# PHR_revA.net
KiCad netlist of a schematic drawn in EAGLE
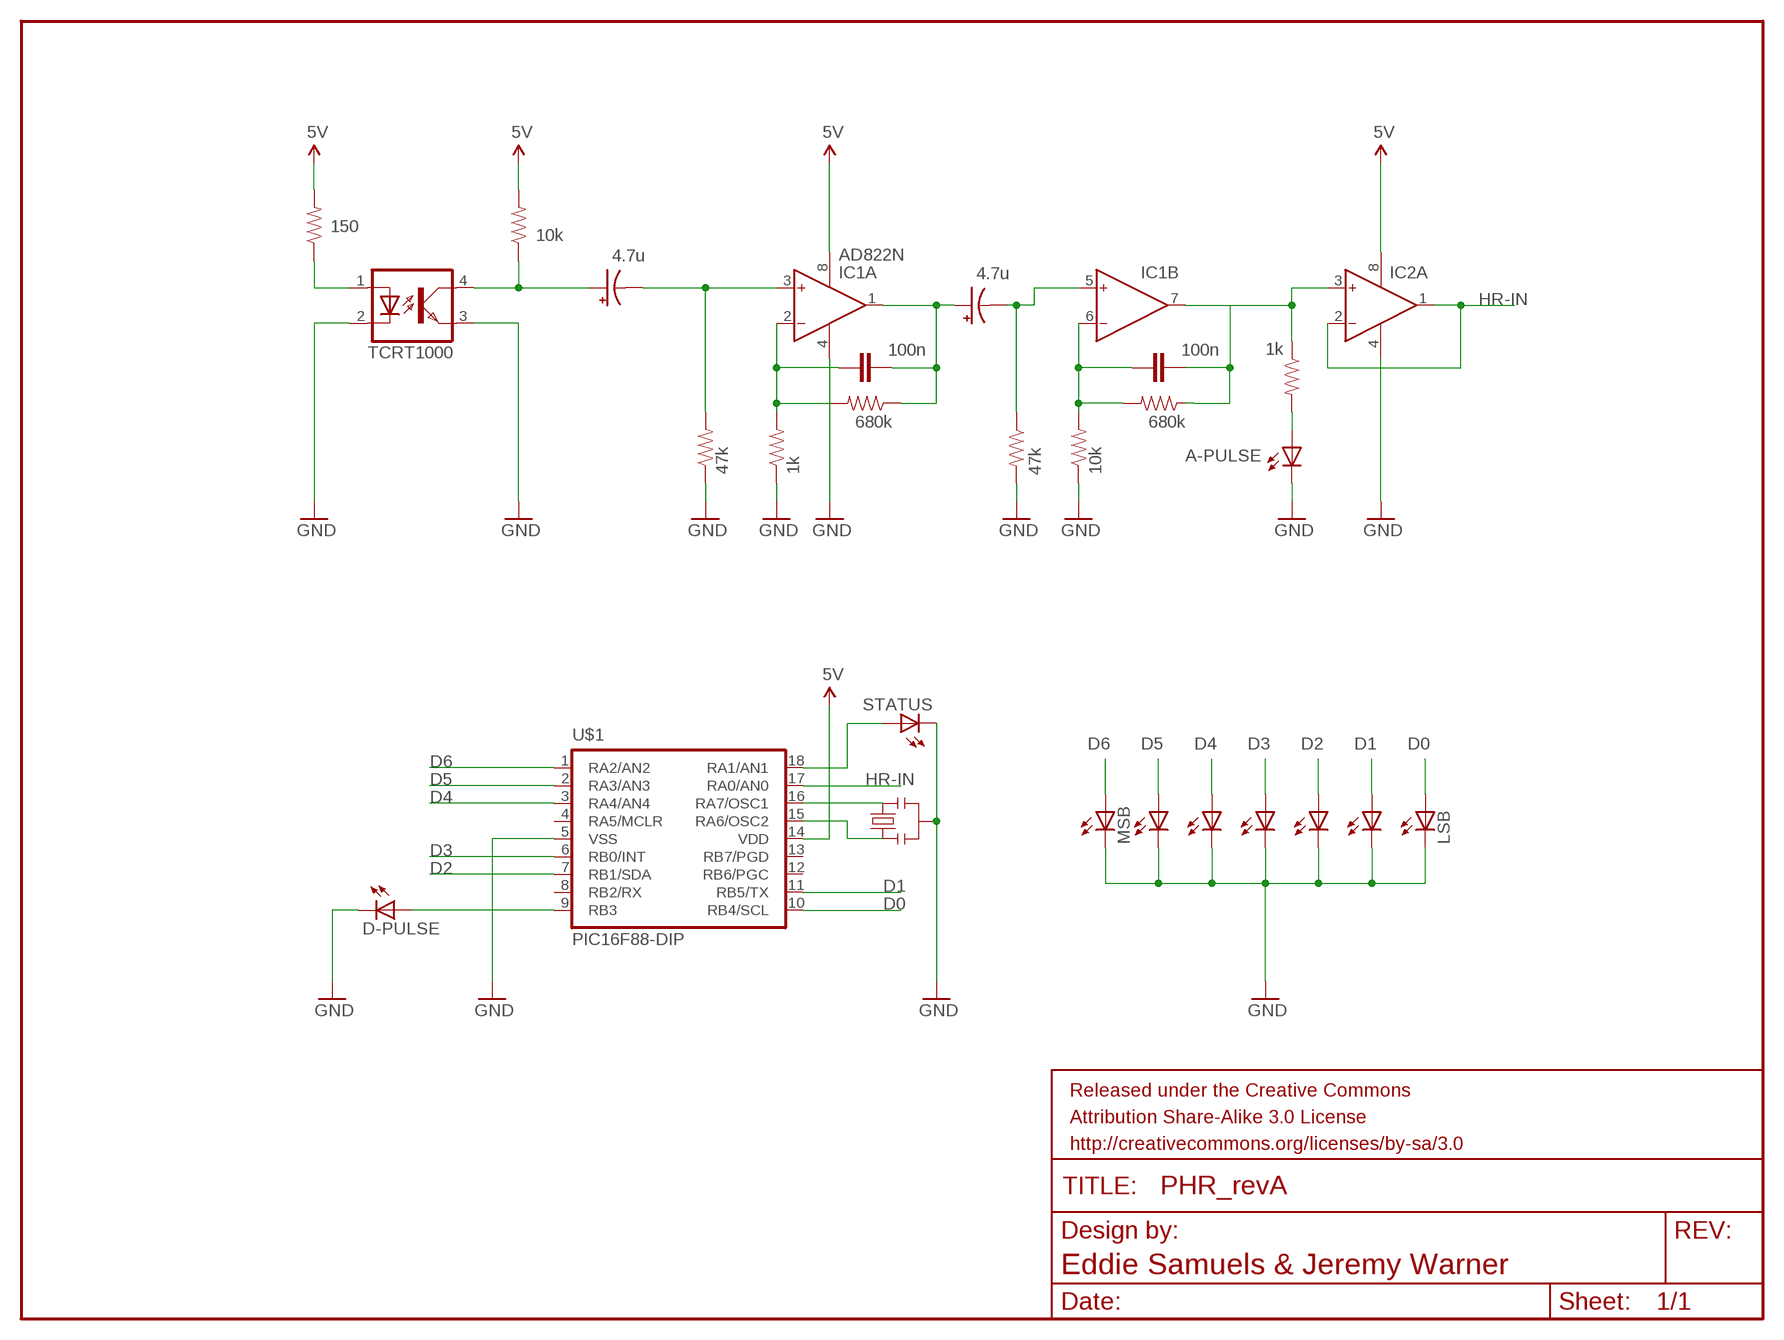
[diagram p0: schematic, sheet 1]

(export (version "E")
  (design (tool "Eeschema 10.0.6"))
  (components
    (comp (ref "A-PULSE")
      (value "LED3MM")
      (footprint "eagle-import:LED3MM")
      (libsource (lib "eagle-import") (part "LED3MM"))
    )
    (comp (ref "C1")
      (value "100n")
      (footprint "eagle-import:CAP-PTH-SMALL-KIT")
      (libsource (lib "eagle-import") (part "CAPKIT"))
    )
    (comp (ref "C2")
      (value "100n")
      (footprint "eagle-import:CAP-PTH-SMALL-KIT")
      (libsource (lib "eagle-import") (part "CAPKIT"))
    )
    (comp (ref "C3")
      (value "4.7u")
      (footprint "eagle-import:CPOL-RADIAL-10UF-25V")
      (libsource (lib "eagle-import") (part "CAP_POLPTH2"))
    )
    (comp (ref "C4")
      (value "4.7u")
      (footprint "eagle-import:CPOL-RADIAL-10UF-25V")
      (libsource (lib "eagle-import") (part "CAP_POLPTH2"))
    )
    (comp (ref "D-PULSE")
      (value "LED3MM")
      (footprint "eagle-import:LED3MM")
      (libsource (lib "eagle-import") (part "LED3MM"))
    )
    (comp (ref "D1")
      (value "LED3MM")
      (footprint "eagle-import:LED3MM")
      (libsource (lib "eagle-import") (part "LED3MM"))
    )
    (comp (ref "D2")
      (value "LED3MM")
      (footprint "eagle-import:LED3MM")
      (libsource (lib "eagle-import") (part "LED3MM"))
    )
    (comp (ref "D3")
      (value "LED3MM")
      (footprint "eagle-import:LED3MM")
      (libsource (lib "eagle-import") (part "LED3MM"))
    )
    (comp (ref "D4")
      (value "LED3MM")
      (footprint "eagle-import:LED3MM")
      (libsource (lib "eagle-import") (part "LED3MM"))
    )
    (comp (ref "D5")
      (value "LED3MM")
      (footprint "eagle-import:LED3MM")
      (libsource (lib "eagle-import") (part "LED3MM"))
    )
    (comp (ref "FRAME1")
      (value "FRAME-LETTER")
      (footprint "eagle-import:CREATIVE_COMMONS")
      (libsource (lib "eagle-import") (part "FRAME-LETTER"))
    )
    (comp (ref "IC1")
      (value "AD822N")
      (footprint "eagle-import:DIL08")
      (libsource (lib "eagle-import") (part "AD822N"))
    )
    (comp (ref "IC2")
      (value "AD822N")
      (footprint "eagle-import:DIL08")
      (libsource (lib "eagle-import") (part "AD822N"))
    )
    (comp (ref "LSB")
      (value "LED3MM")
      (footprint "eagle-import:LED3MM")
      (libsource (lib "eagle-import") (part "LED3MM"))
    )
    (comp (ref "MSB")
      (value "LED3MM")
      (footprint "eagle-import:LED3MM")
      (libsource (lib "eagle-import") (part "LED3MM"))
    )
    (comp (ref "OK1")
      (value "SFH618A-2")
      (footprint "eagle-import:DIP4")
      (fields (field (name "MF") "VISHAY/TELEFUNKEN"))
      (libsource (lib "eagle-import") (part "SFH618?A-2"))
    )
    (comp (ref "R1")
      (value "47k")
      (footprint "eagle-import:AXIAL-0.4")
      (libsource (lib "eagle-import") (part "RESISTORPTH-1/4W"))
    )
    (comp (ref "R2")
      (value "1k")
      (footprint "eagle-import:AXIAL-0.4")
      (libsource (lib "eagle-import") (part "RESISTORPTH-1/4W"))
    )
    (comp (ref "R3")
      (value "680k")
      (footprint "eagle-import:AXIAL-0.4")
      (libsource (lib "eagle-import") (part "RESISTORPTH-1/4W"))
    )
    (comp (ref "R4")
      (value "47k")
      (footprint "eagle-import:AXIAL-0.4")
      (libsource (lib "eagle-import") (part "RESISTORPTH-1/4W"))
    )
    (comp (ref "R5")
      (value "10k")
      (footprint "eagle-import:AXIAL-0.4")
      (libsource (lib "eagle-import") (part "RESISTORPTH-1/4W"))
    )
    (comp (ref "R6")
      (value "680k")
      (footprint "eagle-import:AXIAL-0.4")
      (libsource (lib "eagle-import") (part "RESISTORPTH-1/4W"))
    )
    (comp (ref "R7")
      (value "10k")
      (footprint "eagle-import:AXIAL-0.4")
      (libsource (lib "eagle-import") (part "RESISTORPTH-1/4W"))
    )
    (comp (ref "R8")
      (value "150")
      (footprint "eagle-import:AXIAL-0.4")
      (libsource (lib "eagle-import") (part "RESISTORPTH-1/4W"))
    )
    (comp (ref "R9")
      (value "1k")
      (footprint "eagle-import:AXIAL-0.4")
      (libsource (lib "eagle-import") (part "RESISTORPTH-1/4W"))
    )
    (comp (ref "STATUS")
      (value "LED3MM")
      (footprint "eagle-import:LED3MM")
      (libsource (lib "eagle-import") (part "LED3MM"))
    )
    (comp (ref "U$1")
      (value "PIC16F88-DIP")
      (footprint "eagle-import:DIL18")
      (libsource (lib "eagle-import") (part "PIC16F88-DIP"))
    )
    (comp (ref "Y1")
      (value "RESONATORPTH")
      (footprint "eagle-import:RESONATOR-PTH")
      (libsource (lib "eagle-import") (part "RESONATORPTH"))
    )
  )
  (nets
    (net (code "1") (name "/D0") (class "Default")
      (node (ref "LSB") (pin "A") (pinfunction "A_A") (pintype "passive"))
      (node (ref "U$1") (pin "10") (pinfunction "RB4/SCL_10") (pintype "bidirectional"))
    )
    (net (code "2") (name "/D1") (class "Default")
      (node (ref "D5") (pin "A") (pinfunction "A_A") (pintype "passive"))
      (node (ref "U$1") (pin "11") (pinfunction "RB5/TX_11") (pintype "bidirectional"))
    )
    (net (code "3") (name "/D2") (class "Default")
      (node (ref "D4") (pin "A") (pinfunction "A_A") (pintype "passive"))
      (node (ref "U$1") (pin "7") (pinfunction "RB1/SDA_7") (pintype "bidirectional"))
    )
    (net (code "4") (name "/D3") (class "Default")
      (node (ref "D3") (pin "A") (pinfunction "A_A") (pintype "passive"))
      (node (ref "U$1") (pin "6") (pinfunction "RB0/INT_6") (pintype "bidirectional"))
    )
    (net (code "5") (name "/D4") (class "Default")
      (node (ref "D2") (pin "A") (pinfunction "A_A") (pintype "passive"))
      (node (ref "U$1") (pin "3") (pinfunction "RA4/AN4_3") (pintype "bidirectional"))
    )
    (net (code "6") (name "/D5") (class "Default")
      (node (ref "D1") (pin "A") (pinfunction "A_A") (pintype "passive"))
      (node (ref "U$1") (pin "2") (pinfunction "RA3/AN3_2") (pintype "bidirectional"))
    )
    (net (code "7") (name "/D6") (class "Default")
      (node (ref "MSB") (pin "A") (pinfunction "A_A") (pintype "passive"))
      (node (ref "U$1") (pin "1") (pinfunction "RA2/AN2_1") (pintype "bidirectional"))
    )
    (net (code "8") (name "/HR-IN") (class "Default")
      (node (ref "IC2") (pin "1") (pinfunction "OUT_1") (pintype "output"))
      (node (ref "IC2") (pin "2") (pinfunction "IN-_2") (pintype "input"))
      (node (ref "U$1") (pin "17") (pinfunction "RA0/AN0_17") (pintype "bidirectional"))
    )
    (net (code "9") (name "5V") (class "Default")
      (node (ref "IC1") (pin "8") (pinfunction "V+_8") (pintype "power_in"))
      (node (ref "IC2") (pin "8") (pinfunction "V+_8") (pintype "power_in"))
      (node (ref "R7") (pin "P$2") (pinfunction "2_P$2") (pintype "passive"))
      (node (ref "R8") (pin "P$2") (pinfunction "2_P$2") (pintype "passive"))
      (node (ref "U$1") (pin "14") (pinfunction "VDD_14") (pintype "power_in"))
    )
    (net (code "10") (name "GND") (class "Default")
      (node (ref "A-PULSE") (pin "K") (pinfunction "C_K") (pintype "passive"))
      (node (ref "D-PULSE") (pin "K") (pinfunction "C_K") (pintype "passive"))
      (node (ref "D1") (pin "K") (pinfunction "C_K") (pintype "passive"))
      (node (ref "D2") (pin "K") (pinfunction "C_K") (pintype "passive"))
      (node (ref "D3") (pin "K") (pinfunction "C_K") (pintype "passive"))
      (node (ref "D4") (pin "K") (pinfunction "C_K") (pintype "passive"))
      (node (ref "D5") (pin "K") (pinfunction "C_K") (pintype "passive"))
      (node (ref "IC1") (pin "4") (pinfunction "V-_4") (pintype "power_in"))
      (node (ref "IC2") (pin "4") (pinfunction "V-_4") (pintype "power_in"))
      (node (ref "LSB") (pin "K") (pinfunction "C_K") (pintype "passive"))
      (node (ref "MSB") (pin "K") (pinfunction "C_K") (pintype "passive"))
      (node (ref "OK1") (pin "2") (pinfunction "C_2") (pintype "passive"))
      (node (ref "OK1") (pin "3") (pinfunction "EMIT_3") (pintype "passive"))
      (node (ref "R1") (pin "P$1") (pinfunction "1_P$1") (pintype "passive"))
      (node (ref "R2") (pin "P$1") (pinfunction "1_P$1") (pintype "passive"))
      (node (ref "R4") (pin "P$2") (pinfunction "2_P$2") (pintype "passive"))
      (node (ref "R5") (pin "P$1") (pinfunction "1_P$1") (pintype "passive"))
      (node (ref "STATUS") (pin "K") (pinfunction "C_K") (pintype "passive"))
      (node (ref "U$1") (pin "5") (pinfunction "VSS_5") (pintype "power_in"))
      (node (ref "Y1") (pin "2") (pinfunction "2_2") (pintype "passive"))
    )
    (net (code "11") (name "Net-(C3-+)") (class "Default")
      (node (ref "C3") (pin "1") (pinfunction "+_1") (pintype "passive"))
      (node (ref "OK1") (pin "4") (pinfunction "COL_4") (pintype "passive"))
      (node (ref "R7") (pin "P$1") (pinfunction "1_P$1") (pintype "passive"))
    )
    (net (code "12") (name "Net-(C3--)") (class "Default")
      (node (ref "C3") (pin "2") (pinfunction "-_2") (pintype "passive"))
      (node (ref "IC1") (pin "3") (pinfunction "IN+_3") (pintype "input"))
      (node (ref "R1") (pin "P$2") (pinfunction "2_P$2") (pintype "passive"))
    )
    (net (code "13") (name "Net-(C4-+)") (class "Default")
      (node (ref "C1") (pin "2") (pinfunction "2_2") (pintype "passive"))
      (node (ref "C4") (pin "1") (pinfunction "+_1") (pintype "passive"))
      (node (ref "IC1") (pin "1") (pinfunction "OUT_1") (pintype "output"))
      (node (ref "R3") (pin "P$1") (pinfunction "1_P$1") (pintype "passive"))
    )
    (net (code "14") (name "Net-(C4--)") (class "Default")
      (node (ref "C4") (pin "2") (pinfunction "-_2") (pintype "passive"))
      (node (ref "IC1") (pin "5") (pinfunction "IN+_5") (pintype "input"))
      (node (ref "R4") (pin "P$1") (pinfunction "1_P$1") (pintype "passive"))
    )
    (net (code "15") (name "Net-(IC1A-IN-)") (class "Default")
      (node (ref "C1") (pin "1") (pinfunction "1_1") (pintype "passive"))
      (node (ref "IC1") (pin "2") (pinfunction "IN-_2") (pintype "input"))
      (node (ref "R2") (pin "P$2") (pinfunction "2_P$2") (pintype "passive"))
      (node (ref "R3") (pin "P$2") (pinfunction "2_P$2") (pintype "passive"))
    )
    (net (code "16") (name "Net-(IC1B-IN-)") (class "Default")
      (node (ref "C2") (pin "1") (pinfunction "1_1") (pintype "passive"))
      (node (ref "IC1") (pin "6") (pinfunction "IN-_6") (pintype "input"))
      (node (ref "R5") (pin "P$2") (pinfunction "2_P$2") (pintype "passive"))
      (node (ref "R6") (pin "P$2") (pinfunction "2_P$2") (pintype "passive"))
    )
    (net (code "17") (name "Net-(IC1B-OUT)") (class "Default")
      (node (ref "C2") (pin "2") (pinfunction "2_2") (pintype "passive"))
      (node (ref "IC1") (pin "7") (pinfunction "OUT_7") (pintype "output"))
      (node (ref "IC2") (pin "3") (pinfunction "IN+_3") (pintype "input"))
      (node (ref "R6") (pin "P$1") (pinfunction "1_P$1") (pintype "passive"))
      (node (ref "R9") (pin "P$1") (pinfunction "1_P$1") (pintype "passive"))
    )
    (net (code "18") (name "Net-(OK1-A)") (class "Default")
      (node (ref "OK1") (pin "1") (pinfunction "A_1") (pintype "passive"))
      (node (ref "R8") (pin "P$1") (pinfunction "1_P$1") (pintype "passive"))
    )
    (net (code "19") (name "Net-(R9-2)") (class "Default")
      (node (ref "A-PULSE") (pin "A") (pinfunction "A_A") (pintype "passive"))
      (node (ref "R9") (pin "P$2") (pinfunction "2_P$2") (pintype "passive"))
    )
    (net (code "20") (name "Net-(U$1-RA1{slash}AN1)") (class "Default")
      (node (ref "STATUS") (pin "A") (pinfunction "A_A") (pintype "passive"))
      (node (ref "U$1") (pin "18") (pinfunction "RA1/AN1_18") (pintype "bidirectional"))
    )
    (net (code "21") (name "Net-(U$1-RA6{slash}OSC2)") (class "Default")
      (node (ref "U$1") (pin "15") (pinfunction "RA6/OSC2_15") (pintype "bidirectional"))
      (node (ref "Y1") (pin "1") (pinfunction "1_1") (pintype "passive"))
    )
    (net (code "22") (name "Net-(U$1-RA7{slash}OSC1)") (class "Default")
      (node (ref "U$1") (pin "16") (pinfunction "RA7/OSC1_16") (pintype "bidirectional"))
      (node (ref "Y1") (pin "3") (pinfunction "3_3") (pintype "passive"))
    )
    (net (code "23") (name "Net-(U$1-RB3)") (class "Default")
      (node (ref "D-PULSE") (pin "A") (pinfunction "A_A") (pintype "passive"))
      (node (ref "U$1") (pin "9") (pinfunction "RB3_9") (pintype "bidirectional"))
    )
    (net (code "24") (name "unconnected-(U$1-RA5{slash}MCLR-Pad4)") (class "Default")
      (node (ref "U$1") (pin "4") (pinfunction "RA5/MCLR_4") (pintype "input"))
    )
    (net (code "25") (name "unconnected-(U$1-RB2{slash}RX-Pad8)") (class "Default")
      (node (ref "U$1") (pin "8") (pinfunction "RB2/RX_8") (pintype "bidirectional"))
    )
    (net (code "26") (name "unconnected-(U$1-RB6{slash}PGC-Pad12)") (class "Default")
      (node (ref "U$1") (pin "12") (pinfunction "RB6/PGC_12") (pintype "bidirectional"))
    )
    (net (code "27") (name "unconnected-(U$1-RB7{slash}PGD-Pad13)") (class "Default")
      (node (ref "U$1") (pin "13") (pinfunction "RB7/PGD_13") (pintype "bidirectional"))
    )
  )
)
